# Generic_MOSFET_LVD.net
KiCad netlist of a schematic drawn in EAGLE
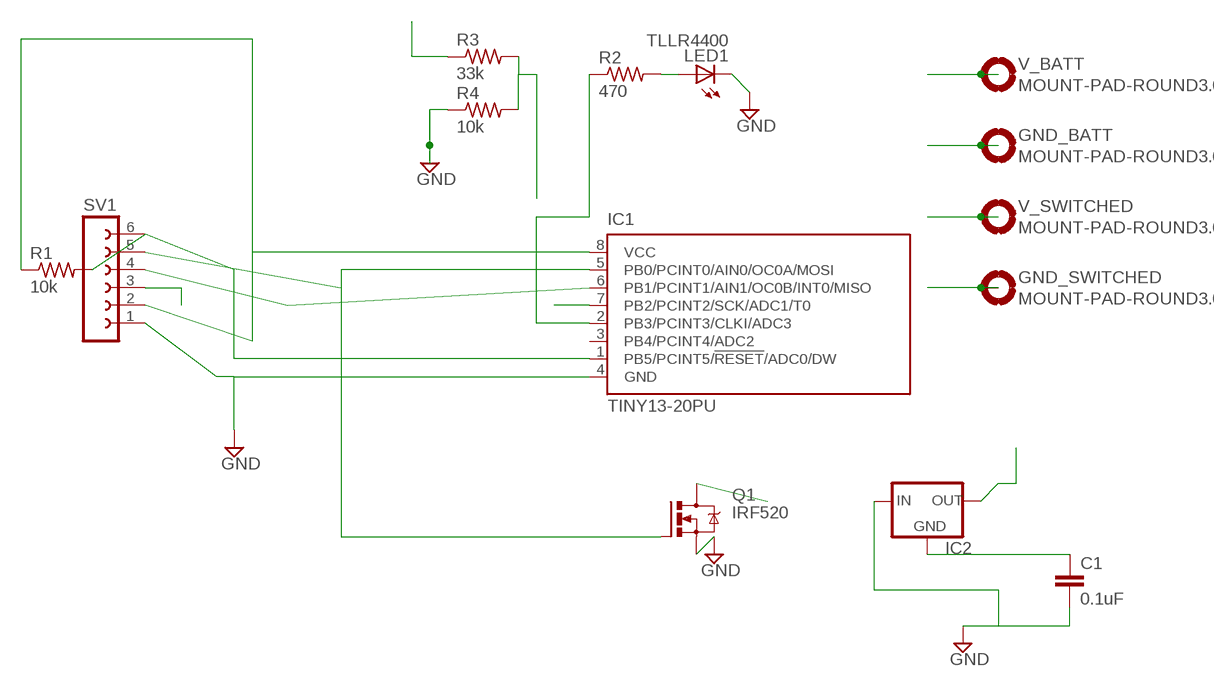
[diagram p0: schematic, sheet 1]

(export (version "E")
  (design (tool "Eeschema 10.0.6"))
  (components
    (comp (ref "C1")
      (value "0.1uF")
      (footprint "eagle-import:C2.5-3")
      (libsource (lib "eagle-import") (part "C2,5-3"))
    )
    (comp (ref "GND_BATT")
      (value "MOUNT-PAD-ROUND3.0")
      (footprint "eagle-import:3,0-PAD")
      (libsource (lib "eagle-import") (part "MOUNT-PAD-ROUND3.0"))
    )
    (comp (ref "GND_SWITCHED")
      (value "MOUNT-PAD-ROUND3.0")
      (footprint "eagle-import:3,0-PAD")
      (libsource (lib "eagle-import") (part "MOUNT-PAD-ROUND3.0"))
    )
    (comp (ref "IC1")
      (value "TINY13-20PU")
      (footprint "eagle-import:DIL08")
      (fields (field (name "MPN") "ATTINY13-20PU"))
      (libsource (lib "eagle-import") (part "TINY13PU-20"))
    )
    (comp (ref "IC2")
      (value "78XXS")
      (footprint "eagle-import:78XXS")
      (libsource (lib "eagle-import") (part "78XXS"))
    )
    (comp (ref "LED1")
      (value "TLLR4400")
      (footprint "eagle-import:LED3MM")
      (fields (field (name "MF") "VISHAY SEMICONDUCTOR"))
      (libsource (lib "eagle-import") (part "TLLR4400"))
    )
    (comp (ref "Q1")
      (value "IRF520")
      (footprint "eagle-import:TO220BV")
      (libsource (lib "eagle-import") (part "IRF520"))
    )
    (comp (ref "R1")
      (value "10k")
      (footprint "eagle-import:0204_5")
      (libsource (lib "eagle-import") (part "R-US_0204/5"))
    )
    (comp (ref "R2")
      (value "470")
      (footprint "eagle-import:0204_5")
      (libsource (lib "eagle-import") (part "R-US_0204/5"))
    )
    (comp (ref "R3")
      (value "33k")
      (footprint "eagle-import:0204_5")
      (libsource (lib "eagle-import") (part "R-US_0204/5"))
    )
    (comp (ref "R4")
      (value "10k")
      (footprint "eagle-import:0204_5")
      (libsource (lib "eagle-import") (part "R-US_0204/5"))
    )
    (comp (ref "SV1")
      (value "FE06-1")
      (footprint "eagle-import:FE06")
      (libsource (lib "eagle-import") (part "FE06-1"))
    )
    (comp (ref "V_BATT")
      (value "MOUNT-PAD-ROUND3.0")
      (footprint "eagle-import:3,0-PAD")
      (libsource (lib "eagle-import") (part "MOUNT-PAD-ROUND3.0"))
    )
    (comp (ref "V_SWITCHED")
      (value "MOUNT-PAD-ROUND3.0")
      (footprint "eagle-import:3,0-PAD")
      (libsource (lib "eagle-import") (part "MOUNT-PAD-ROUND3.0"))
    )
  )
  (nets
    (net (code "1") (name "/GND_SWITCHED") (class "Default")
      (node (ref "GND_SWITCHED") (pin "B3,0") (pinfunction "MOUNT_B3,0") (pintype "passive"))
      (node (ref "Q1") (pin "D") (pinfunction "D_D") (pintype "passive"))
    )
    (net (code "2") (name "/VCC") (class "Default")
      (node (ref "C1") (pin "1") (pinfunction "1_1") (pintype "passive"))
      (node (ref "IC1") (pin "8") (pinfunction "VCC_8") (pintype "power_in"))
      (node (ref "IC2") (pin "GND") (pinfunction "GND_GND") (pintype "input"))
      (node (ref "R1") (pin "1") (pinfunction "1_1") (pintype "passive"))
      (node (ref "SV1") (pin "2") (pinfunction "2_2") (pintype "passive"))
    )
    (net (code "3") (name "/V_BATT") (class "Default")
      (node (ref "IC2") (pin "OUT") (pinfunction "OUT_OUT") (pintype "passive"))
      (node (ref "R3") (pin "1") (pinfunction "1_1") (pintype "passive"))
      (node (ref "V_BATT") (pin "B3,0") (pinfunction "MOUNT_B3,0") (pintype "passive"))
      (node (ref "V_SWITCHED") (pin "B3,0") (pinfunction "MOUNT_B3,0") (pintype "passive"))
    )
    (net (code "4") (name "/V_SENSE") (class "Default")
      (node (ref "IC1") (pin "7") (pinfunction "PB2/PCINT2/SCK/ADC1/T0_7") (pintype "bidirectional"))
      (node (ref "R3") (pin "2") (pinfunction "2_2") (pintype "passive"))
      (node (ref "R4") (pin "2") (pinfunction "2_2") (pintype "passive"))
      (node (ref "SV1") (pin "3") (pinfunction "3_3") (pintype "passive"))
    )
    (net (code "5") (name "GND") (class "Default")
      (node (ref "C1") (pin "2") (pinfunction "2_2") (pintype "passive"))
      (node (ref "GND_BATT") (pin "B3,0") (pinfunction "MOUNT_B3,0") (pintype "passive"))
      (node (ref "IC1") (pin "4") (pinfunction "GND_4") (pintype "power_in"))
      (node (ref "IC2") (pin "IN") (pinfunction "IN_IN") (pintype "input"))
      (node (ref "LED1") (pin "K") (pinfunction "C_K") (pintype "passive"))
      (node (ref "Q1") (pin "S") (pinfunction "S_S") (pintype "passive"))
      (node (ref "R4") (pin "1") (pinfunction "1_1") (pintype "passive"))
      (node (ref "SV1") (pin "1") (pinfunction "1_1") (pintype "passive"))
    )
    (net (code "6") (name "Net-(IC1-PB0{slash}PCINT0{slash}AIN0{slash}OC0A{slash}MOSI)") (class "Default")
      (node (ref "IC1") (pin "5") (pinfunction "PB0/PCINT0/AIN0/OC0A/MOSI_5") (pintype "bidirectional"))
      (node (ref "Q1") (pin "G") (pinfunction "G_G") (pintype "passive"))
      (node (ref "SV1") (pin "5") (pinfunction "5_5") (pintype "passive"))
    )
    (net (code "7") (name "Net-(IC1-PB1{slash}PCINT1{slash}AIN1{slash}OC0B{slash}INT0{slash}MISO)") (class "Default")
      (node (ref "IC1") (pin "6") (pinfunction "PB1/PCINT1/AIN1/OC0B/INT0/MISO_6") (pintype "bidirectional"))
      (node (ref "SV1") (pin "4") (pinfunction "4_4") (pintype "passive"))
    )
    (net (code "8") (name "Net-(IC1-PB3{slash}PCINT3{slash}CLKI{slash}ADC3)") (class "Default")
      (node (ref "IC1") (pin "2") (pinfunction "PB3/PCINT3/CLKI/ADC3_2") (pintype "bidirectional"))
      (node (ref "R2") (pin "1") (pinfunction "1_1") (pintype "passive"))
    )
    (net (code "9") (name "Net-(IC1-PB5{slash}PCINT5{slash}~{RESET}{slash}ADC0{slash}DW)") (class "Default")
      (node (ref "IC1") (pin "1") (pinfunction "PB5/PCINT5/~{RESET}/ADC0/DW_1") (pintype "bidirectional"))
      (node (ref "R1") (pin "2") (pinfunction "2_2") (pintype "passive"))
      (node (ref "SV1") (pin "6") (pinfunction "6_6") (pintype "passive"))
    )
    (net (code "10") (name "Net-(LED1-PadA)") (class "Default")
      (node (ref "LED1") (pin "A") (pinfunction "A_A") (pintype "passive"))
      (node (ref "R2") (pin "2") (pinfunction "2_2") (pintype "passive"))
    )
    (net (code "11") (name "unconnected-(IC1-PB4{slash}PCINT4{slash}ADC2-Pad3)") (class "Default")
      (node (ref "IC1") (pin "3") (pinfunction "PB4/PCINT4/ADC2_3") (pintype "bidirectional"))
    )
  )
)
